# Power3_3V.net
KiCad netlist of a schematic drawn in Altium Designer
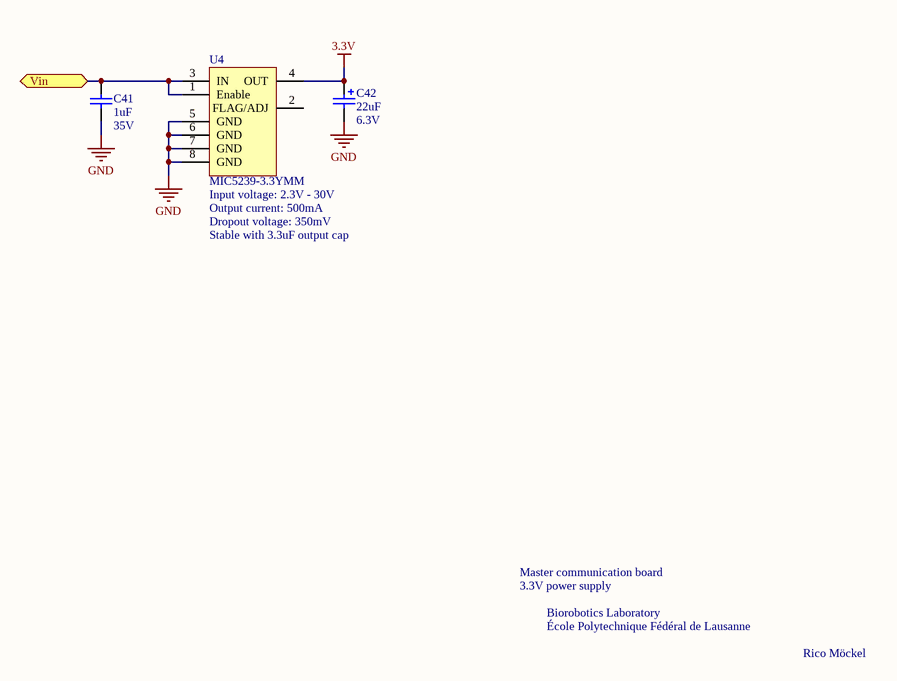
[diagram p0: Power3.3V.SchDoc]

(export (version "E")
  (design (tool "Eeschema 10.0.6"))
  (components
    (comp (ref "C41")
      (value "1uF")
      (footprint "CAPC1608N")
      (description "Capacitor")
      (fields
        (field (name "VOLTAGE") "35V")
        (field (name "Comment") "1uF, 35V")
        (field (name "PUBLISHER") "Altium Limited")
      )
      (libsource (lib "Miscellaneous Devices") (part "Cap"))
    )
    (comp (ref "C42")
      (value "22uF")
      (footprint "1608-10")
      (description "Polarized Capacitor")
      (fields
        (field (name "VOLTAGE") "6.3V")
        (field (name "Comment") "22uF, 6.3V")
        (field (name "PUBLISHER") "Altium Limited")
      )
      (libsource (lib "Miscellaneous Devices") (part "Cap Pol2"))
    )
    (comp (ref "U4")
      (value "MIC5239-3.3YMM")
      (footprint "MSOP-8")
      (description "LDO, 500mA, Vin:2.3V-30V")
      (libsource (lib "Roombots") (part "MIC5239"))
    )
  )
  (nets
    (net (code "1") (name "/Vin") (class "Default")
      (node (ref "C41") (pin "2") (pinfunction "2_2") (pintype "passive"))
      (node (ref "U4") (pin "1") (pinfunction "Enable_1") (pintype "passive"))
      (node (ref "U4") (pin "3") (pinfunction "IN_3") (pintype "power_in"))
    )
    (net (code "2") (name "3.3V") (class "Default")
      (node (ref "C42") (pin "1") (pinfunction "1_1") (pintype "passive"))
      (node (ref "U4") (pin "4") (pinfunction "OUT_4") (pintype "power_in"))
    )
    (net (code "3") (name "GND") (class "Default")
      (node (ref "C41") (pin "1") (pinfunction "1_1") (pintype "passive"))
      (node (ref "C42") (pin "2") (pinfunction "2_2") (pintype "passive"))
      (node (ref "U4") (pin "5") (pinfunction "GND_5") (pintype "power_in"))
      (node (ref "U4") (pin "6") (pinfunction "GND_6") (pintype "power_in"))
      (node (ref "U4") (pin "7") (pinfunction "GND_7") (pintype "power_in"))
      (node (ref "U4") (pin "8") (pinfunction "GND_8") (pintype "power_in"))
    )
    (net (code "4") (name "unconnected-(U4-FLAG{slash}ADJ-Pad2)") (class "Default")
      (node (ref "U4") (pin "2") (pinfunction "FLAG/ADJ_2") (pintype "passive"))
    )
  )
)
